# garage_monitor.net
KiCad netlist of a schematic drawn in EAGLE
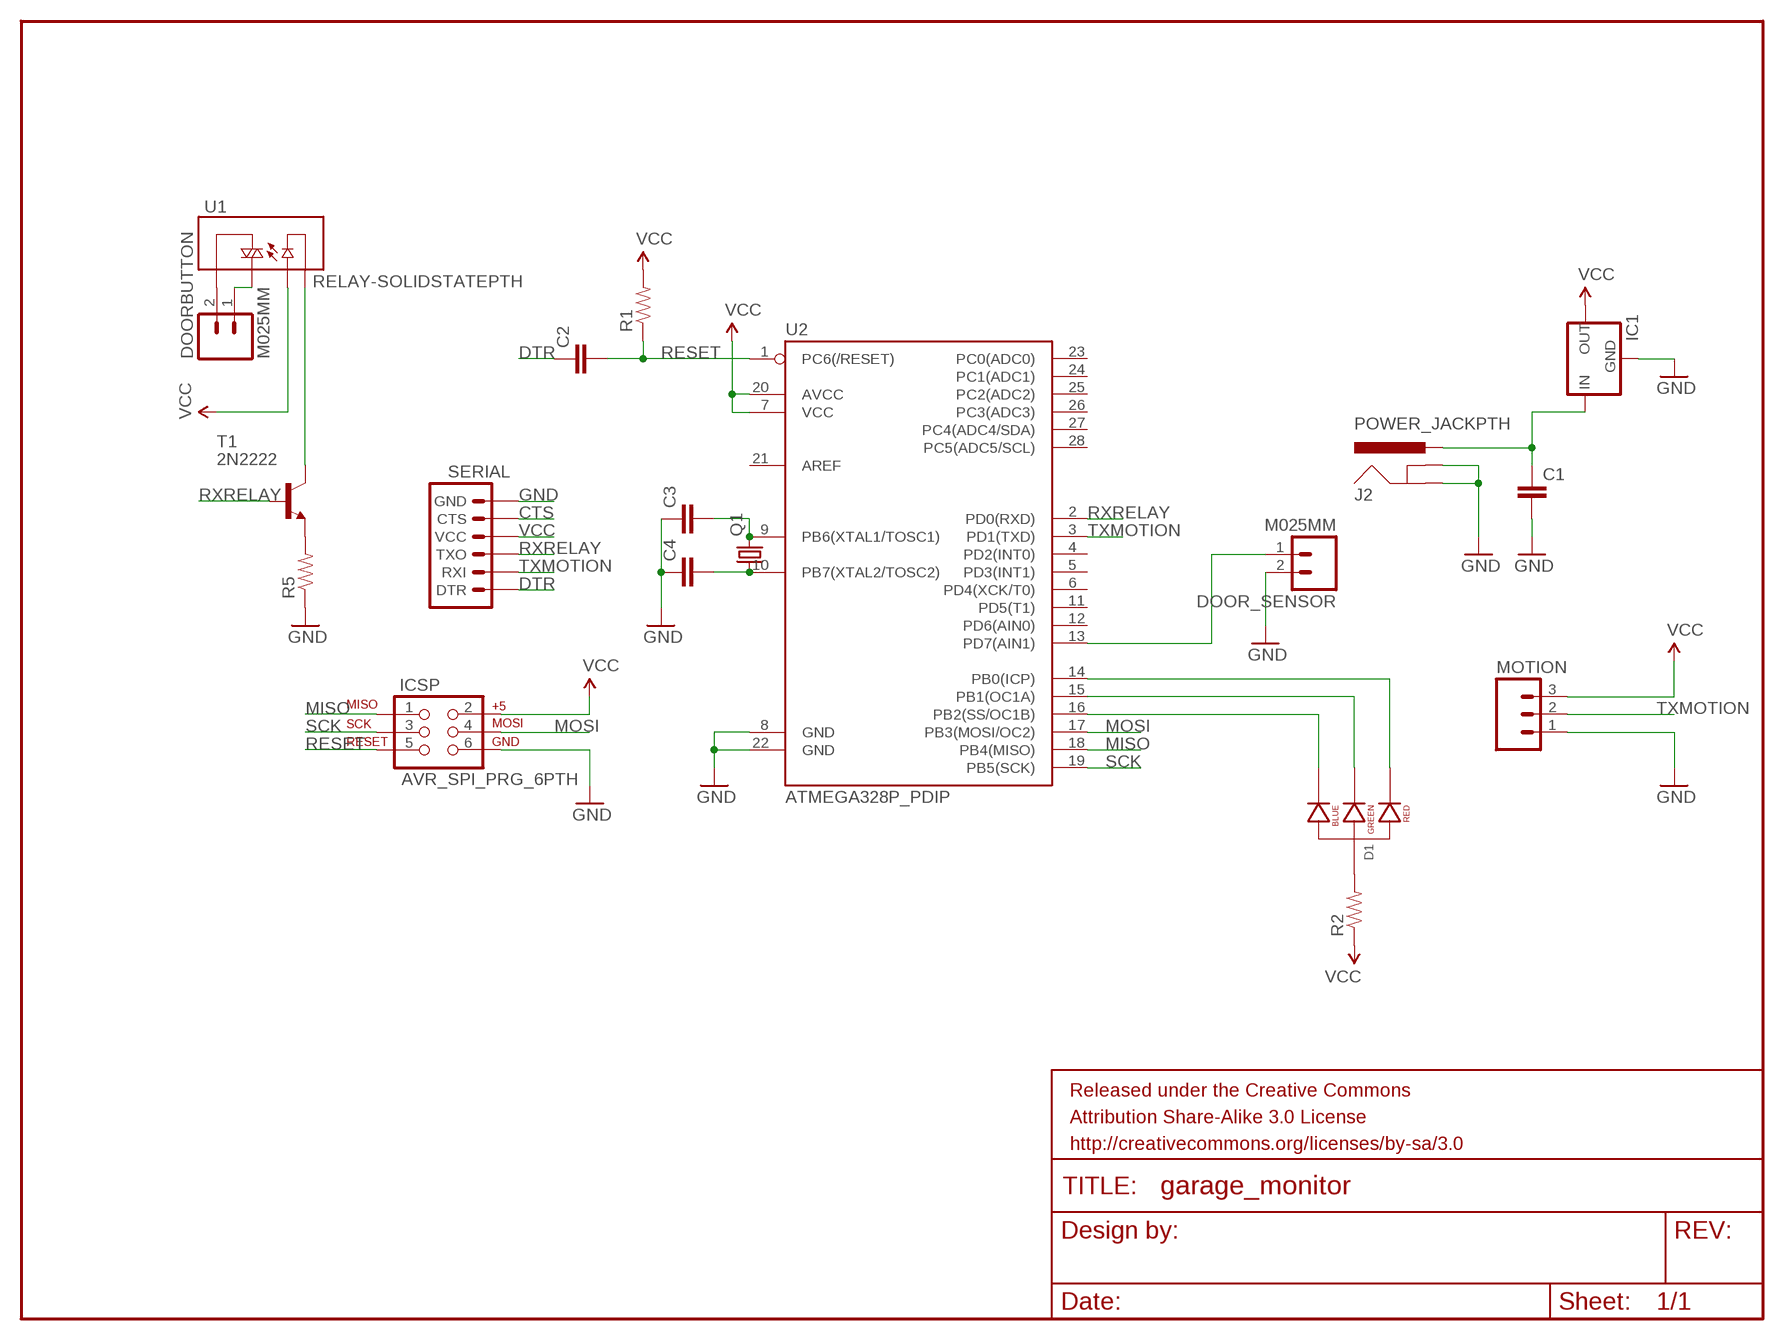
[diagram p0: schematic, sheet 1]

(export (version "E")
  (design (tool "Eeschema 10.0.6"))
  (components
    (comp (ref "C1")
      (value "CAPPTH")
      (footprint "eagle-import:CAP-PTH-SMALL")
      (libsource (lib "eagle-import") (part "CAPPTH"))
    )
    (comp (ref "C2")
      (value "CAPPTH")
      (footprint "eagle-import:CAP-PTH-SMALL")
      (libsource (lib "eagle-import") (part "CAPPTH"))
    )
    (comp (ref "C3")
      (value "CAPEZ")
      (footprint "eagle-import:CAP-PTH-SMALLEZ")
      (libsource (lib "eagle-import") (part "CAPEZ"))
    )
    (comp (ref "C4")
      (value "CAPEZ")
      (footprint "eagle-import:CAP-PTH-SMALLEZ")
      (libsource (lib "eagle-import") (part "CAPEZ"))
    )
    (comp (ref "D1")
      (value "LED-RGB-CA-THRUCLEAR")
      (footprint "eagle-import:LED-RGB-THRU")
      (libsource (lib "eagle-import") (part "LED-RGB-CA-THRUCLEAR"))
    )
    (comp (ref "DOORBUTTON")
      (value "M025MM")
      (footprint "eagle-import:SCREWTERMINAL-5MM-2")
      (libsource (lib "eagle-import") (part "M025MM"))
    )
    (comp (ref "DOOR_SENSOR")
      (value "M025MM")
      (footprint "eagle-import:SCREWTERMINAL-5MM-2")
      (libsource (lib "eagle-import") (part "M025MM"))
    )
    (comp (ref "FRAME1")
      (value "FRAME-LETTER")
      (footprint "eagle-import:CREATIVE_COMMONS")
      (libsource (lib "eagle-import") (part "FRAME-LETTER"))
    )
    (comp (ref "IC1")
      (value "V_REG_78XXSIDE")
      (footprint "eagle-import:78XXL")
      (libsource (lib "eagle-import") (part "V_REG_78XXSIDE"))
    )
    (comp (ref "ICSP")
      (value "AVR_SPI_PRG_6PTH")
      (footprint "eagle-import:2X3")
      (libsource (lib "eagle-import") (part "AVR_SPI_PRG_6PTH"))
    )
    (comp (ref "J2")
      (value "POWER_JACKPTH")
      (footprint "eagle-import:POWER_JACK_PTH")
      (libsource (lib "eagle-import") (part "POWER_JACKPTH"))
    )
    (comp (ref "MOTION")
      (value "M03PTH")
      (footprint "eagle-import:1X03")
      (libsource (lib "eagle-import") (part "M03PTH"))
    )
    (comp (ref "Q1")
      (value "CRYSTALHC49S")
      (footprint "eagle-import:HC49_S")
      (libsource (lib "eagle-import") (part "CRYSTALHC49S"))
    )
    (comp (ref "R1")
      (value "RESISTORPTH-1/4W")
      (footprint "eagle-import:AXIAL-0.4")
      (libsource (lib "eagle-import") (part "RESISTORPTH-1/4W"))
    )
    (comp (ref "R2")
      (value "RESISTORPTH-1/4W")
      (footprint "eagle-import:AXIAL-0.4")
      (libsource (lib "eagle-import") (part "RESISTORPTH-1/4W"))
    )
    (comp (ref "R5")
      (value "RESISTORPTH-1/4W")
      (footprint "eagle-import:AXIAL-0.4")
      (libsource (lib "eagle-import") (part "RESISTORPTH-1/4W"))
    )
    (comp (ref "SERIAL")
      (value "ARDUINO_SERIAL_PROGRAMPTH")
      (footprint "eagle-import:1X06")
      (libsource (lib "eagle-import") (part "ARDUINO_SERIAL_PROGRAMPTH"))
    )
    (comp (ref "T1")
      (value "2N2222")
      (footprint "eagle-import:TO18")
      (libsource (lib "eagle-import") (part "2N2222"))
    )
    (comp (ref "U1")
      (value "RELAY-SOLIDSTATEPTH")
      (footprint "eagle-import:RELAY-S108T02")
      (libsource (lib "eagle-import") (part "RELAY-SOLIDSTATEPTH"))
    )
    (comp (ref "U2")
      (value "ATMEGA328P_PDIP")
      (footprint "eagle-import:DIL28-3")
      (libsource (lib "eagle-import") (part "ATMEGA328P_PDIP"))
    )
  )
  (nets
    (net (code "1") (name "/CTS") (class "Default")
      (node (ref "SERIAL") (pin "5") (pinfunction "CTS_5") (pintype "passive"))
    )
    (net (code "2") (name "/DTR") (class "Default")
      (node (ref "C2") (pin "1") (pinfunction "1_1") (pintype "passive"))
      (node (ref "SERIAL") (pin "1") (pinfunction "DTR_1") (pintype "passive"))
    )
    (net (code "3") (name "/MISO") (class "Default")
      (node (ref "ICSP") (pin "1") (pinfunction "1_1") (pintype "passive"))
      (node (ref "U2") (pin "18") (pinfunction "PB4(MISO)_18") (pintype "bidirectional"))
    )
    (net (code "4") (name "/MOSI") (class "Default")
      (node (ref "ICSP") (pin "4") (pinfunction "4_4") (pintype "passive"))
      (node (ref "U2") (pin "17") (pinfunction "PB3(MOSI/OC2)_17") (pintype "bidirectional"))
    )
    (net (code "5") (name "/RESET") (class "Default")
      (node (ref "C2") (pin "2") (pinfunction "2_2") (pintype "passive"))
      (node (ref "ICSP") (pin "5") (pinfunction "5_5") (pintype "passive"))
      (node (ref "R1") (pin "P$1") (pinfunction "1_P$1") (pintype "passive"))
      (node (ref "U2") (pin "1") (pinfunction "PC6(/RESET)_1") (pintype "bidirectional"))
    )
    (net (code "6") (name "/RXRELAY") (class "Default")
      (node (ref "SERIAL") (pin "3") (pinfunction "TXO_3") (pintype "passive"))
      (node (ref "T1") (pin "2") (pinfunction "B_2") (pintype "passive"))
      (node (ref "U2") (pin "2") (pinfunction "PD0(RXD)_2") (pintype "bidirectional"))
    )
    (net (code "7") (name "/SCK") (class "Default")
      (node (ref "ICSP") (pin "3") (pinfunction "3_3") (pintype "passive"))
      (node (ref "U2") (pin "19") (pinfunction "PB5(SCK)_19") (pintype "bidirectional"))
    )
    (net (code "8") (name "/TXMOTION") (class "Default")
      (node (ref "MOTION") (pin "2") (pinfunction "2_2") (pintype "passive"))
      (node (ref "SERIAL") (pin "2") (pinfunction "RXI_2") (pintype "passive"))
      (node (ref "U2") (pin "3") (pinfunction "PD1(TXD)_3") (pintype "bidirectional"))
    )
    (net (code "9") (name "GND") (class "Default")
      (node (ref "C1") (pin "2") (pinfunction "2_2") (pintype "passive"))
      (node (ref "C3") (pin "1") (pinfunction "1_1") (pintype "passive"))
      (node (ref "C4") (pin "1") (pinfunction "1_1") (pintype "passive"))
      (node (ref "DOOR_SENSOR") (pin "2") (pinfunction "2_2") (pintype "passive"))
      (node (ref "IC1") (pin "GND") (pinfunction "GND_GND") (pintype "input"))
      (node (ref "ICSP") (pin "6") (pinfunction "6_6") (pintype "passive"))
      (node (ref "J2") (pin "GND") (pinfunction "GND_GND") (pintype "bidirectional"))
      (node (ref "J2") (pin "GNDBREAK") (pinfunction "GNDBREAK_GNDBREAK") (pintype "bidirectional"))
      (node (ref "MOTION") (pin "1") (pinfunction "1_1") (pintype "passive"))
      (node (ref "R5") (pin "P$1") (pinfunction "1_P$1") (pintype "passive"))
      (node (ref "SERIAL") (pin "6") (pinfunction "GND_6") (pintype "passive"))
      (node (ref "U2") (pin "22") (pinfunction "GND_22") (pintype "bidirectional"))
      (node (ref "U2") (pin "8") (pinfunction "GND_8") (pintype "bidirectional"))
    )
    (net (code "10") (name "Net-(C1-Pad1)") (class "Default")
      (node (ref "C1") (pin "1") (pinfunction "1_1") (pintype "passive"))
      (node (ref "IC1") (pin "IN") (pinfunction "IN_IN") (pintype "input"))
      (node (ref "J2") (pin "PWR") (pinfunction "PWR_PWR") (pintype "bidirectional"))
    )
    (net (code "11") (name "Net-(D1-ANODE)") (class "Default")
      (node (ref "D1") (pin "2") (pinfunction "ANODE_2") (pintype "bidirectional"))
      (node (ref "R2") (pin "P$2") (pinfunction "2_P$2") (pintype "passive"))
    )
    (net (code "12") (name "Net-(D1-BLUE_CATHODE)") (class "Default")
      (node (ref "D1") (pin "4") (pinfunction "BLUE_CATHODE_4") (pintype "bidirectional"))
      (node (ref "U2") (pin "16") (pinfunction "PB2(SS/OC1B)_16") (pintype "bidirectional"))
    )
    (net (code "13") (name "Net-(D1-GREEN_CATHODE)") (class "Default")
      (node (ref "D1") (pin "3") (pinfunction "GREEN_CATHODE_3") (pintype "bidirectional"))
      (node (ref "U2") (pin "15") (pinfunction "PB1(OC1A)_15") (pintype "bidirectional"))
    )
    (net (code "14") (name "Net-(D1-RED_CATHODE)") (class "Default")
      (node (ref "D1") (pin "1") (pinfunction "RED_CATHODE_1") (pintype "bidirectional"))
      (node (ref "U2") (pin "14") (pinfunction "PB0(ICP)_14") (pintype "bidirectional"))
    )
    (net (code "15") (name "Net-(R5-2)") (class "Default")
      (node (ref "R5") (pin "P$2") (pinfunction "2_P$2") (pintype "passive"))
      (node (ref "T1") (pin "1") (pinfunction "E_1") (pintype "passive"))
    )
    (net (code "16") (name "Net-(T1-C)") (class "Default")
      (node (ref "T1") (pin "3") (pinfunction "C_3") (pintype "passive"))
      (node (ref "U1") (pin "4") (pinfunction "-_4") (pintype "bidirectional"))
    )
    (net (code "17") (name "Net-(U1-T1)") (class "Default")
      (node (ref "DOORBUTTON") (pin "2") (pinfunction "2_2") (pintype "passive"))
      (node (ref "U1") (pin "1") (pinfunction "T1_1") (pintype "bidirectional"))
    )
    (net (code "18") (name "Net-(U1-T2)") (class "Default")
      (node (ref "DOORBUTTON") (pin "1") (pinfunction "1_1") (pintype "passive"))
      (node (ref "U1") (pin "2") (pinfunction "T2_2") (pintype "bidirectional"))
    )
    (net (code "19") (name "Net-(U2-PB6(XTAL1{slash}TOSC1))") (class "Default")
      (node (ref "C3") (pin "2") (pinfunction "2_2") (pintype "passive"))
      (node (ref "Q1") (pin "2") (pinfunction "2_2") (pintype "passive"))
      (node (ref "U2") (pin "9") (pinfunction "PB6(XTAL1/TOSC1)_9") (pintype "bidirectional"))
    )
    (net (code "20") (name "Net-(U2-PB7(XTAL2{slash}TOSC2))") (class "Default")
      (node (ref "C4") (pin "2") (pinfunction "2_2") (pintype "passive"))
      (node (ref "Q1") (pin "1") (pinfunction "1_1") (pintype "passive"))
      (node (ref "U2") (pin "10") (pinfunction "PB7(XTAL2/TOSC2)_10") (pintype "bidirectional"))
    )
    (net (code "21") (name "Net-(U2-PD7(AIN1))") (class "Default")
      (node (ref "DOOR_SENSOR") (pin "1") (pinfunction "1_1") (pintype "passive"))
      (node (ref "U2") (pin "13") (pinfunction "PD7(AIN1)_13") (pintype "bidirectional"))
    )
    (net (code "22") (name "VCC") (class "Default")
      (node (ref "IC1") (pin "OUT") (pinfunction "OUT_OUT") (pintype "output"))
      (node (ref "ICSP") (pin "2") (pinfunction "2_2") (pintype "passive"))
      (node (ref "MOTION") (pin "3") (pinfunction "3_3") (pintype "passive"))
      (node (ref "R1") (pin "P$2") (pinfunction "2_P$2") (pintype "passive"))
      (node (ref "R2") (pin "P$1") (pinfunction "1_P$1") (pintype "passive"))
      (node (ref "SERIAL") (pin "4") (pinfunction "VCC_4") (pintype "passive"))
      (node (ref "U1") (pin "3") (pinfunction "+_3") (pintype "bidirectional"))
      (node (ref "U2") (pin "20") (pinfunction "AVCC_20") (pintype "bidirectional"))
      (node (ref "U2") (pin "7") (pinfunction "VCC_7") (pintype "bidirectional"))
    )
    (net (code "23") (name "unconnected-(U2-AREF-Pad21)") (class "Default")
      (node (ref "U2") (pin "21") (pinfunction "AREF_21") (pintype "bidirectional"))
    )
    (net (code "24") (name "unconnected-(U2-PC0(ADC0)-Pad23)") (class "Default")
      (node (ref "U2") (pin "23") (pinfunction "PC0(ADC0)_23") (pintype "bidirectional"))
    )
    (net (code "25") (name "unconnected-(U2-PC1(ADC1)-Pad24)") (class "Default")
      (node (ref "U2") (pin "24") (pinfunction "PC1(ADC1)_24") (pintype "bidirectional"))
    )
    (net (code "26") (name "unconnected-(U2-PC2(ADC2)-Pad25)") (class "Default")
      (node (ref "U2") (pin "25") (pinfunction "PC2(ADC2)_25") (pintype "bidirectional"))
    )
    (net (code "27") (name "unconnected-(U2-PC3(ADC3)-Pad26)") (class "Default")
      (node (ref "U2") (pin "26") (pinfunction "PC3(ADC3)_26") (pintype "bidirectional"))
    )
    (net (code "28") (name "unconnected-(U2-PC4(ADC4{slash}SDA)-Pad27)") (class "Default")
      (node (ref "U2") (pin "27") (pinfunction "PC4(ADC4/SDA)_27") (pintype "bidirectional"))
    )
    (net (code "29") (name "unconnected-(U2-PC5(ADC5{slash}SCL)-Pad28)") (class "Default")
      (node (ref "U2") (pin "28") (pinfunction "PC5(ADC5/SCL)_28") (pintype "bidirectional"))
    )
    (net (code "30") (name "unconnected-(U2-PD2(INT0)-Pad4)") (class "Default")
      (node (ref "U2") (pin "4") (pinfunction "PD2(INT0)_4") (pintype "bidirectional"))
    )
    (net (code "31") (name "unconnected-(U2-PD3(INT1)-Pad5)") (class "Default")
      (node (ref "U2") (pin "5") (pinfunction "PD3(INT1)_5") (pintype "bidirectional"))
    )
    (net (code "32") (name "unconnected-(U2-PD4(XCK{slash}T0)-Pad6)") (class "Default")
      (node (ref "U2") (pin "6") (pinfunction "PD4(XCK/T0)_6") (pintype "bidirectional"))
    )
    (net (code "33") (name "unconnected-(U2-PD5(T1)-Pad11)") (class "Default")
      (node (ref "U2") (pin "11") (pinfunction "PD5(T1)_11") (pintype "bidirectional"))
    )
    (net (code "34") (name "unconnected-(U2-PD6(AIN0)-Pad12)") (class "Default")
      (node (ref "U2") (pin "12") (pinfunction "PD6(AIN0)_12") (pintype "bidirectional"))
    )
  )
)
